# serial_to_LCD.net
KiCad netlist of a schematic drawn in EAGLE
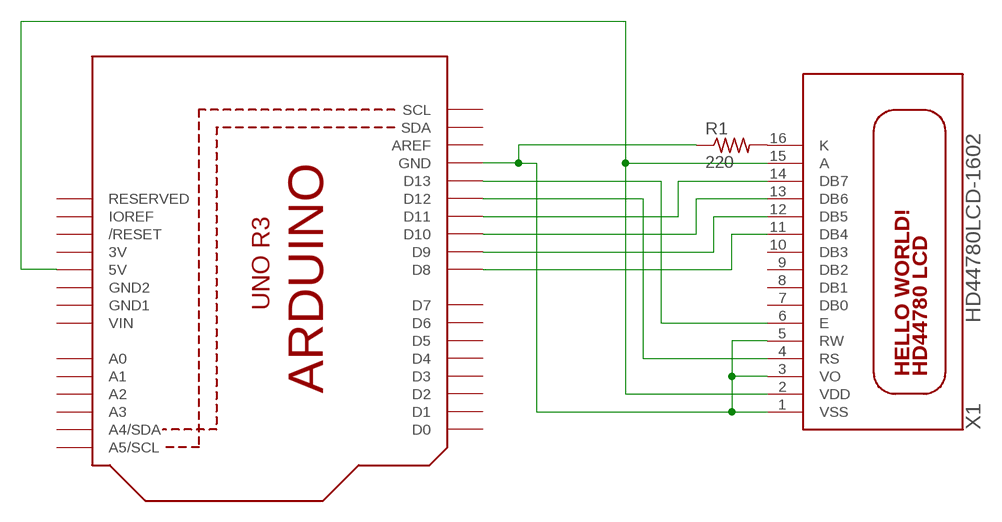
[diagram p0: schematic, sheet 1]

(export (version "E")
  (design (tool "Eeschema 10.0.6"))
  (components
    (comp (ref "R1")
      (value "220")
      (footprint "eagle-import:0204_5")
      (libsource (lib "eagle-import") (part "R-US_0204/5"))
    )
    (comp (ref "U1")
      (value "ARDUINOR3-DIMENSION")
      (footprint "eagle-import:ARDUINOR3")
      (libsource (lib "eagle-import") (part "ARDUINOR3-DIMENSION"))
    )
    (comp (ref "X1")
      (value "HD44780LCD-1602")
      (footprint "eagle-import:LCD1602")
      (libsource (lib "eagle-import") (part "HD44780LCD-1602"))
    )
  )
  (nets
    (net (code "1") (name "/3V") (class "Default")
      (node (ref "U1") (pin "3V") (pinfunction "3V_3V") (pintype "power_in"))
    )
    (net (code "2") (name "/GND1") (class "Default")
      (node (ref "U1") (pin "GND1") (pinfunction "GND1_GND1") (pintype "power_in"))
    )
    (net (code "3") (name "/GND2") (class "Default")
      (node (ref "U1") (pin "GND2") (pinfunction "GND2_GND2") (pintype "power_in"))
    )
    (net (code "4") (name "/VIN") (class "Default")
      (node (ref "U1") (pin "VIN") (pinfunction "VIN_VIN") (pintype "power_in"))
    )
    (net (code "5") (name "Net-(X1-A)") (class "Default")
      (node (ref "U1") (pin "5V") (pinfunction "5V_5V") (pintype "power_in"))
      (node (ref "X1") (pin "15") (pinfunction "A_15") (pintype "input"))
      (node (ref "X1") (pin "2") (pinfunction "VDD_2") (pintype "power_in"))
    )
    (net (code "6") (name "Net-(X1-DB4)") (class "Default")
      (node (ref "U1") (pin "D8") (pinfunction "D8_D8") (pintype "bidirectional"))
      (node (ref "X1") (pin "11") (pinfunction "DB4_11") (pintype "bidirectional"))
    )
    (net (code "7") (name "Net-(X1-DB5)") (class "Default")
      (node (ref "U1") (pin "D9") (pinfunction "D9_D9") (pintype "bidirectional"))
      (node (ref "X1") (pin "12") (pinfunction "DB5_12") (pintype "bidirectional"))
    )
    (net (code "8") (name "Net-(X1-DB6)") (class "Default")
      (node (ref "U1") (pin "D10") (pinfunction "D10_D10") (pintype "bidirectional"))
      (node (ref "X1") (pin "13") (pinfunction "DB6_13") (pintype "bidirectional"))
    )
    (net (code "9") (name "Net-(X1-DB7)") (class "Default")
      (node (ref "U1") (pin "D11") (pinfunction "D11_D11") (pintype "bidirectional"))
      (node (ref "X1") (pin "14") (pinfunction "DB7_14") (pintype "bidirectional"))
    )
    (net (code "10") (name "Net-(X1-E)") (class "Default")
      (node (ref "U1") (pin "D13") (pinfunction "D13_D13") (pintype "bidirectional"))
      (node (ref "X1") (pin "6") (pinfunction "E_6") (pintype "input"))
    )
    (net (code "11") (name "Net-(X1-K)") (class "Default")
      (node (ref "R1") (pin "2") (pinfunction "2_2") (pintype "passive"))
      (node (ref "X1") (pin "16") (pinfunction "K_16") (pintype "input"))
    )
    (net (code "12") (name "Net-(X1-RS)") (class "Default")
      (node (ref "U1") (pin "D12") (pinfunction "D12_D12") (pintype "bidirectional"))
      (node (ref "X1") (pin "4") (pinfunction "RS_4") (pintype "input"))
    )
    (net (code "13") (name "Net-(X1-RW)") (class "Default")
      (node (ref "R1") (pin "1") (pinfunction "1_1") (pintype "passive"))
      (node (ref "U1") (pin "GND") (pinfunction "GND_GND") (pintype "power_in"))
      (node (ref "X1") (pin "1") (pinfunction "VSS_1") (pintype "power_in"))
      (node (ref "X1") (pin "3") (pinfunction "VO_3") (pintype "input"))
      (node (ref "X1") (pin "5") (pinfunction "RW_5") (pintype "input"))
    )
    (net (code "14") (name "unconnected-(U1-A4{slash}SDA-PadA4)") (class "Default")
      (node (ref "U1") (pin "A4") (pinfunction "A4/SDA_A4") (pintype "bidirectional"))
    )
    (net (code "15") (name "unconnected-(U1-A5{slash}SCL-PadA5)") (class "Default")
      (node (ref "U1") (pin "A5") (pinfunction "A5/SCL_A5") (pintype "bidirectional"))
    )
    (net (code "16") (name "unconnected-(U1-PadA0)") (class "Default")
      (node (ref "U1") (pin "A0") (pinfunction "A0_A0") (pintype "bidirectional"))
    )
    (net (code "17") (name "unconnected-(U1-PadA1)") (class "Default")
      (node (ref "U1") (pin "A1") (pinfunction "A1_A1") (pintype "bidirectional"))
    )
    (net (code "18") (name "unconnected-(U1-PadA2)") (class "Default")
      (node (ref "U1") (pin "A2") (pinfunction "A2_A2") (pintype "bidirectional"))
    )
    (net (code "19") (name "unconnected-(U1-PadA3)") (class "Default")
      (node (ref "U1") (pin "A3") (pinfunction "A3_A3") (pintype "bidirectional"))
    )
    (net (code "20") (name "unconnected-(U1-PadAREF)") (class "Default")
      (node (ref "U1") (pin "AREF") (pinfunction "AREF_AREF") (pintype "bidirectional"))
    )
    (net (code "21") (name "unconnected-(U1-PadD0)") (class "Default")
      (node (ref "U1") (pin "D0") (pinfunction "D0_D0") (pintype "bidirectional"))
    )
    (net (code "22") (name "unconnected-(U1-PadD1)") (class "Default")
      (node (ref "U1") (pin "D1") (pinfunction "D1_D1") (pintype "bidirectional"))
    )
    (net (code "23") (name "unconnected-(U1-PadD2)") (class "Default")
      (node (ref "U1") (pin "D2") (pinfunction "D2_D2") (pintype "bidirectional"))
    )
    (net (code "24") (name "unconnected-(U1-PadD3)") (class "Default")
      (node (ref "U1") (pin "D3") (pinfunction "D3_D3") (pintype "bidirectional"))
    )
    (net (code "25") (name "unconnected-(U1-PadD4)") (class "Default")
      (node (ref "U1") (pin "D4") (pinfunction "D4_D4") (pintype "bidirectional"))
    )
    (net (code "26") (name "unconnected-(U1-PadD5)") (class "Default")
      (node (ref "U1") (pin "D5") (pinfunction "D5_D5") (pintype "bidirectional"))
    )
    (net (code "27") (name "unconnected-(U1-PadD6)") (class "Default")
      (node (ref "U1") (pin "D6") (pinfunction "D6_D6") (pintype "bidirectional"))
    )
    (net (code "28") (name "unconnected-(U1-PadD7)") (class "Default")
      (node (ref "U1") (pin "D7") (pinfunction "D7_D7") (pintype "bidirectional"))
    )
    (net (code "29") (name "unconnected-(U1-PadIOREF)") (class "Default")
      (node (ref "U1") (pin "IOREF") (pinfunction "IOREF_IOREF") (pintype "output"))
    )
    (net (code "30") (name "unconnected-(U1-PadRESERVED)") (class "Default")
      (node (ref "U1") (pin "RESERVED") (pinfunction "RESERVED_RESERVED") (pintype "no_connect"))
    )
    (net (code "31") (name "unconnected-(U1-PadSCL)") (class "Default")
      (node (ref "U1") (pin "SCL") (pinfunction "SCL_SCL") (pintype "bidirectional"))
    )
    (net (code "32") (name "unconnected-(U1-PadSDA)") (class "Default")
      (node (ref "U1") (pin "SDA") (pinfunction "SDA_SDA") (pintype "bidirectional"))
    )
    (net (code "33") (name "unconnected-(U1-{slash}RESET-PadRESET)") (class "Default")
      (node (ref "U1") (pin "RESET") (pinfunction "/RESET_RESET") (pintype "bidirectional"))
    )
    (net (code "34") (name "unconnected-(X1-DB0-Pad7)") (class "Default")
      (node (ref "X1") (pin "7") (pinfunction "DB0_7") (pintype "bidirectional"))
    )
    (net (code "35") (name "unconnected-(X1-DB1-Pad8)") (class "Default")
      (node (ref "X1") (pin "8") (pinfunction "DB1_8") (pintype "bidirectional"))
    )
    (net (code "36") (name "unconnected-(X1-DB2-Pad9)") (class "Default")
      (node (ref "X1") (pin "9") (pinfunction "DB2_9") (pintype "bidirectional"))
    )
    (net (code "37") (name "unconnected-(X1-DB3-Pad10)") (class "Default")
      (node (ref "X1") (pin "10") (pinfunction "DB3_10") (pintype "bidirectional"))
    )
  )
)
